# USB.net
KiCad netlist of a schematic drawn in Altium Designer
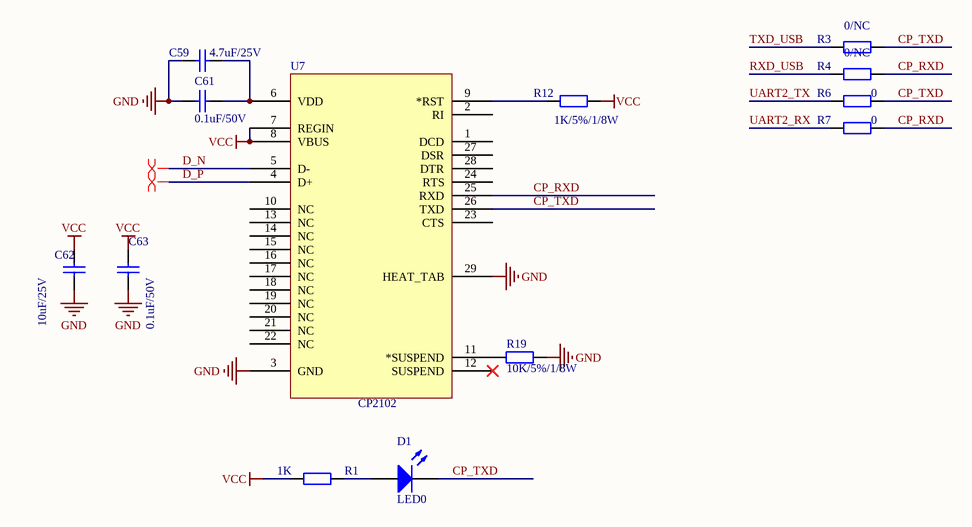
[diagram p0: USB.SchDoc]

(export (version "E")
  (design (tool "Eeschema 10.0.6"))
  (components
    (comp (ref "C59")
      (value "4.7uF/25V")
      (footprint "0603C")
      (description "Capacitor")
      (fields (field (name "PUBLISHER") "Altium Limited"))
      (libsource (lib "Miscellaneous Devices") (part "Cap"))
    )
    (comp (ref "C61")
      (value "0.1uF/50V")
      (footprint "0402C")
      (description "Capacitor")
      (fields (field (name "PUBLISHER") "Altium Limited"))
      (libsource (lib "Miscellaneous Devices") (part "Cap"))
    )
    (comp (ref "C62")
      (value "10uF/25V")
      (footprint "0603C")
      (description "Capacitor")
      (fields (field (name "PUBLISHER") "Altium Limited"))
      (libsource (lib "Miscellaneous Devices") (part "Cap"))
    )
    (comp (ref "C63")
      (value "0.1uF/50V")
      (footprint "0402C")
      (description "Capacitor")
      (fields (field (name "PUBLISHER") "Altium Limited"))
      (libsource (lib "Miscellaneous Devices") (part "Cap"))
    )
    (comp (ref "D1")
      (value "LED0")
      (footprint "0603LED")
      (description "Typical INFRARED GaAs LED")
      (fields (field (name "PUBLISHER") "Altium Limited"))
      (libsource (lib "Miscellaneous Devices") (part "LED0"))
    )
    (comp (ref "R1")
      (value "1K")
      (footprint "0402R")
      (description "Resistor SMD - IEC symbol version")
      (libsource (lib "SX1276_e266v02a") (part "Resistor"))
    )
    (comp (ref "R3")
      (value "0/NC")
      (footprint "0402R")
      (description "Resistor")
      (fields (field (name "PUBLISHER") "Altium Limited"))
      (libsource (lib "Miscellaneous Devices") (part "Res2"))
    )
    (comp (ref "R4")
      (value "0/NC")
      (footprint "0402R")
      (description "Resistor")
      (fields (field (name "PUBLISHER") "Altium Limited"))
      (libsource (lib "Miscellaneous Devices") (part "Res2"))
    )
    (comp (ref "R6")
      (value "0")
      (footprint "0402R")
      (description "Resistor")
      (fields (field (name "PUBLISHER") "Altium Limited"))
      (libsource (lib "Miscellaneous Devices") (part "Res2"))
    )
    (comp (ref "R7")
      (value "0")
      (footprint "0402R")
      (description "Resistor")
      (fields (field (name "PUBLISHER") "Altium Limited"))
      (libsource (lib "Miscellaneous Devices") (part "Res2"))
    )
    (comp (ref "R12")
      (value "1K/5%/1/8W")
      (footprint "0402R")
      (description "Resistor")
      (fields (field (name "PUBLISHER") "Altium Limited"))
      (libsource (lib "Miscellaneous Devices") (part "Res2"))
    )
    (comp (ref "R19")
      (value "10K/5%/1/8W")
      (footprint "0402R")
      (description "Resistor")
      (fields (field (name "PUBLISHER") "Altium Limited"))
      (libsource (lib "Miscellaneous Devices") (part "Res2"))
    )
    (comp (ref "U7")
      (value "CP2102")
      (footprint "QFN28N5X5-0p5P-L")
      (description "Imported")
      (libsource (lib "stm32") (part "CP2102"))
    )
  )
  (nets
    (net (code "1") (name "/CP_RXD") (class "Default")
      (node (ref "R4") (pin "1") (pinfunction "1_1") (pintype "passive"))
      (node (ref "R7") (pin "1") (pinfunction "1_1") (pintype "passive"))
      (node (ref "U7") (pin "25") (pinfunction "RXD_25") (pintype "passive"))
    )
    (net (code "2") (name "/CP_TXD") (class "Default")
      (node (ref "D1") (pin "2") (pinfunction "K_2") (pintype "passive"))
      (node (ref "R3") (pin "1") (pinfunction "1_1") (pintype "passive"))
      (node (ref "R6") (pin "1") (pinfunction "1_1") (pintype "passive"))
      (node (ref "U7") (pin "26") (pinfunction "TXD_26") (pintype "passive"))
    )
    (net (code "3") (name "/D_N") (class "Default")
      (node (ref "U7") (pin "5") (pinfunction "D-_5") (pintype "passive"))
    )
    (net (code "4") (name "/D_P") (class "Default")
      (node (ref "U7") (pin "4") (pinfunction "D+_4") (pintype "passive"))
    )
    (net (code "5") (name "/RXD_USB") (class "Default")
      (node (ref "R4") (pin "2") (pinfunction "2_2") (pintype "passive"))
    )
    (net (code "6") (name "/TXD_USB") (class "Default")
      (node (ref "R3") (pin "2") (pinfunction "2_2") (pintype "passive"))
    )
    (net (code "7") (name "/UART2_RX") (class "Default")
      (node (ref "R7") (pin "2") (pinfunction "2_2") (pintype "passive"))
    )
    (net (code "8") (name "/UART2_TX") (class "Default")
      (node (ref "R6") (pin "2") (pinfunction "2_2") (pintype "passive"))
    )
    (net (code "9") (name "GND") (class "Default")
      (node (ref "C59") (pin "1") (pinfunction "1_1") (pintype "passive"))
      (node (ref "C61") (pin "2") (pinfunction "2_2") (pintype "passive"))
      (node (ref "C62") (pin "2") (pinfunction "2_2") (pintype "passive"))
      (node (ref "C63") (pin "2") (pinfunction "2_2") (pintype "passive"))
      (node (ref "R19") (pin "1") (pinfunction "1_1") (pintype "passive"))
      (node (ref "U7") (pin "29") (pinfunction "HEAT_TAB_29") (pintype "passive"))
      (node (ref "U7") (pin "3") (pinfunction "GND_3") (pintype "passive"))
    )
    (net (code "10") (name "Net-(D1-A)") (class "Default")
      (node (ref "D1") (pin "1") (pinfunction "A_1") (pintype "passive"))
      (node (ref "R1") (pin "2") (pinfunction "2_2") (pintype "passive"))
    )
    (net (code "11") (name "Net-(U7-*RST)") (class "Default")
      (node (ref "R12") (pin "2") (pinfunction "2_2") (pintype "passive"))
      (node (ref "U7") (pin "9") (pinfunction "*RST_9") (pintype "passive"))
    )
    (net (code "12") (name "Net-(U7-*SUSPEND)") (class "Default")
      (node (ref "R19") (pin "2") (pinfunction "2_2") (pintype "passive"))
      (node (ref "U7") (pin "11") (pinfunction "*SUSPEND_11") (pintype "passive"))
    )
    (net (code "13") (name "Net-(U7-VDD)") (class "Default")
      (node (ref "C59") (pin "2") (pinfunction "2_2") (pintype "passive"))
      (node (ref "C61") (pin "1") (pinfunction "1_1") (pintype "passive"))
      (node (ref "U7") (pin "6") (pinfunction "VDD_6") (pintype "passive"))
    )
    (net (code "14") (name "VCC") (class "Default")
      (node (ref "C62") (pin "1") (pinfunction "1_1") (pintype "passive"))
      (node (ref "C63") (pin "1") (pinfunction "1_1") (pintype "passive"))
      (node (ref "R1") (pin "1") (pinfunction "1_1") (pintype "passive"))
      (node (ref "R12") (pin "1") (pinfunction "1_1") (pintype "passive"))
      (node (ref "U7") (pin "7") (pinfunction "REGIN_7") (pintype "passive"))
      (node (ref "U7") (pin "8") (pinfunction "VBUS_8") (pintype "passive"))
    )
    (net (code "15") (name "unconnected-(U7-CTS-Pad23)") (class "Default")
      (node (ref "U7") (pin "23") (pinfunction "CTS_23") (pintype "passive"))
    )
    (net (code "16") (name "unconnected-(U7-DCD-Pad1)") (class "Default")
      (node (ref "U7") (pin "1") (pinfunction "DCD_1") (pintype "passive"))
    )
    (net (code "17") (name "unconnected-(U7-DSR-Pad27)") (class "Default")
      (node (ref "U7") (pin "27") (pinfunction "DSR_27") (pintype "passive"))
    )
    (net (code "18") (name "unconnected-(U7-DTR-Pad28)") (class "Default")
      (node (ref "U7") (pin "28") (pinfunction "DTR_28") (pintype "passive"))
    )
    (net (code "19") (name "unconnected-(U7-NC-Pad10)") (class "Default")
      (node (ref "U7") (pin "10") (pinfunction "NC_10") (pintype "passive"))
    )
    (net (code "20") (name "unconnected-(U7-NC-Pad13)") (class "Default")
      (node (ref "U7") (pin "13") (pinfunction "NC_13") (pintype "passive"))
    )
    (net (code "21") (name "unconnected-(U7-NC-Pad14)") (class "Default")
      (node (ref "U7") (pin "14") (pinfunction "NC_14") (pintype "passive"))
    )
    (net (code "22") (name "unconnected-(U7-NC-Pad15)") (class "Default")
      (node (ref "U7") (pin "15") (pinfunction "NC_15") (pintype "passive"))
    )
    (net (code "23") (name "unconnected-(U7-NC-Pad16)") (class "Default")
      (node (ref "U7") (pin "16") (pinfunction "NC_16") (pintype "passive"))
    )
    (net (code "24") (name "unconnected-(U7-NC-Pad17)") (class "Default")
      (node (ref "U7") (pin "17") (pinfunction "NC_17") (pintype "passive"))
    )
    (net (code "25") (name "unconnected-(U7-NC-Pad18)") (class "Default")
      (node (ref "U7") (pin "18") (pinfunction "NC_18") (pintype "passive"))
    )
    (net (code "26") (name "unconnected-(U7-NC-Pad19)") (class "Default")
      (node (ref "U7") (pin "19") (pinfunction "NC_19") (pintype "passive"))
    )
    (net (code "27") (name "unconnected-(U7-NC-Pad20)") (class "Default")
      (node (ref "U7") (pin "20") (pinfunction "NC_20") (pintype "passive"))
    )
    (net (code "28") (name "unconnected-(U7-NC-Pad21)") (class "Default")
      (node (ref "U7") (pin "21") (pinfunction "NC_21") (pintype "passive"))
    )
    (net (code "29") (name "unconnected-(U7-NC-Pad22)") (class "Default")
      (node (ref "U7") (pin "22") (pinfunction "NC_22") (pintype "passive"))
    )
    (net (code "30") (name "unconnected-(U7-RI-Pad2)") (class "Default")
      (node (ref "U7") (pin "2") (pinfunction "RI_2") (pintype "passive"))
    )
    (net (code "31") (name "unconnected-(U7-RTS-Pad24)") (class "Default")
      (node (ref "U7") (pin "24") (pinfunction "RTS_24") (pintype "passive"))
    )
    (net (code "32") (name "unconnected-(U7-SUSPEND-Pad12)") (class "Default")
      (node (ref "U7") (pin "12") (pinfunction "SUSPEND_12") (pintype "passive+no_connect"))
    )
  )
)
